# TSAL.net
KiCad netlist of a schematic drawn in Altium Designer
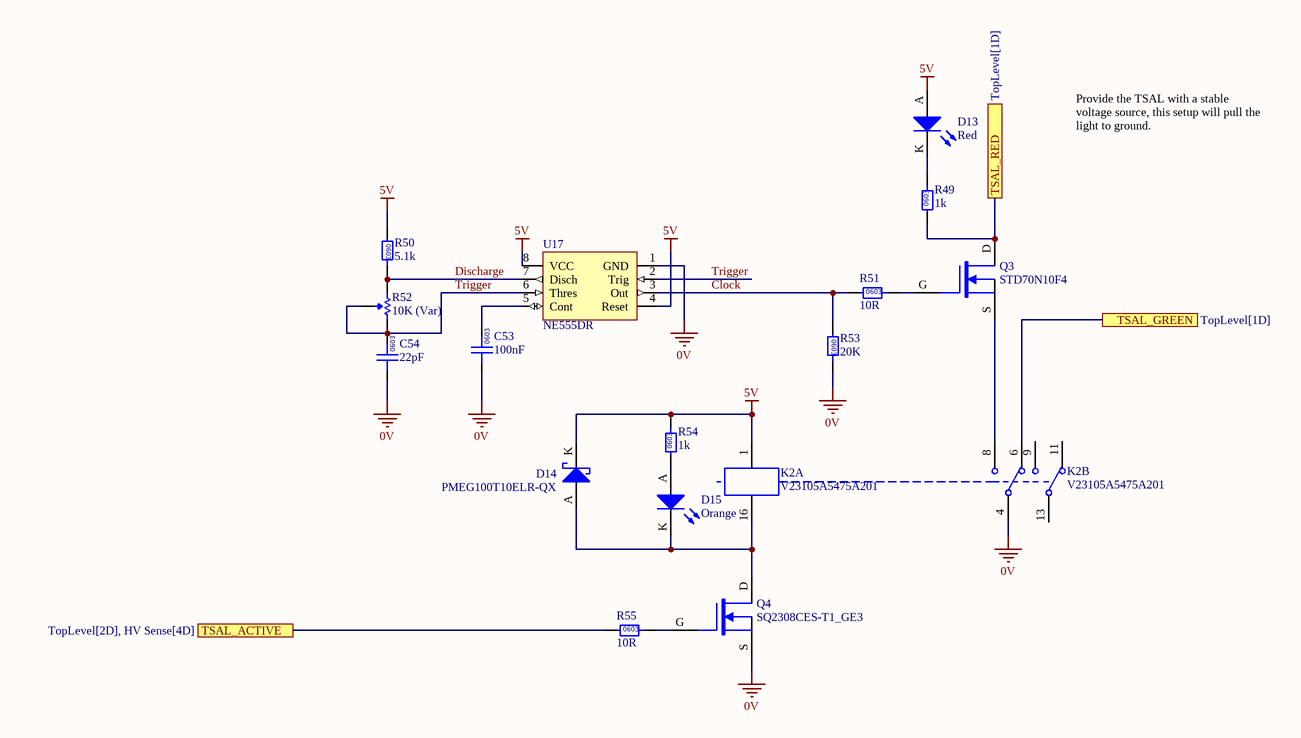
[diagram p0: TSAL.SchDoc]

(export (version "E")
  (design (tool "Eeschema 10.0.6"))
  (components
    (comp (ref "C53")
      (value "100nF")
      (footprint "0603")
      (fields
        (field (name "PART NUMBER") "GCM188L81H104KA57D")
        (field (name "MANUFACTURER") "muRata")
        (field (name "TOLERANCE") "±10%")
      )
      (libsource (lib "ts_standard_library") (part "Capacitor 0603"))
    )
    (comp (ref "C54")
      (value "22pF")
      (footprint "0603")
      (fields
        (field (name "PART NUMBER") "GRM0335C1H220JA01D")
        (field (name "MANUFACTURER") "Murata Electronics")
        (field (name "TOLERANCE") "±5%")
      )
      (libsource (lib "ts_standard_library") (part "Capacitor 0603"))
    )
    (comp (ref "D13")
      (value "Red")
      (footprint "0805 LED")
      (description "Red LED Indication - Discrete 1.75V 0805 (2012 Metric)")
      (fields (field (name "PART NUMBER") "SML-210LTT86") (field (name "MANUFACTURER") "ROHM Semiconductor"))
      (libsource (lib "ts_standard_library") (part "LED"))
    )
    (comp (ref "D14")
      (value "PMEG100T10ELR-QX")
      (footprint "NXP SOD123W")
      (fields
        (field (name "MANUFACTURER") "Nexperia USA Inc.")
        (field (name "DIGIKEY PART NUMBER") "1727-PMEG100T10ELR-QXCT-ND")
      )
      (libsource (lib "ts_standard_library") (part "Diode (Schottky)"))
    )
    (comp (ref "D15")
      (value "Orange")
      (footprint "0805 LED")
      (description "Orange LED Indication - Discrete 1.75V 0805 (2012 Metric)")
      (fields (field (name "PART NUMBER") "SML-211DTT86") (field (name "MANUFACTURER") "ROHM Semiconductor"))
      (libsource (lib "ts_standard_library") (part "LED"))
    )
    (comp (ref "K2")
      (value "V23105A5475A201")
      (footprint "TI 2-DIL")
      (description "5V DPDT Relay 3A 220VDC")
      (libsource (lib "") (part "Symbol_1"))
    )
    (comp (ref "Q3")
      (value "STD70N10F4")
      (footprint "STM TO-252 MOSFET")
      (description "N-Channel 100V 60A (Tc) 125W (Tc) Surface Mount DPAK")
      (fields
        (field (name "MANUFACTURER") "STMicroelectronics")
        (field (name "DIGIKEY PART NUMBER") "497-8806-2-ND")
        (field (name "PUBLISHER") "Altium Limited")
      )
      (libsource (lib "ts_standard_library") (part "MOSFET-N"))
    )
    (comp (ref "Q4")
      (value "SQ2308CES-T1_GE3")
      (footprint "VSHY SOT-23-3")
      (description "MOSFET N-CH 60V 2.3A SOT23")
      (fields
        (field (name "MANUFACTURER") "Vishay Siliconix")
        (field (name "DIGIKEY PART NUMBER") "SQ2308CES-T1_GE3CT-ND")
        (field (name "PUBLISHER") "Altium Limited")
      )
      (libsource (lib "ts_standard_library") (part "MOSFET-N"))
    )
    (comp (ref "R49")
      (value "1k")
      (footprint "0603")
      (fields
        (field (name "PART NUMBER") "RC0603FR-071KL")
        (field (name "MANUFACTURER") "YAGEO")
        (field (name "TOLERANCE") "0.01")
      )
      (libsource (lib "ts_standard_library") (part "Resistor 0603"))
    )
    (comp (ref "R50")
      (value "5.1k")
      (footprint "0603")
      (fields
        (field (name "PART NUMBER") "RC0603JR-075K1L")
        (field (name "MANUFACTURER") "YAGEO")
        (field (name "TOLERANCE") "0.01")
      )
      (libsource (lib "ts_standard_library") (part "Resistor 0603"))
    )
    (comp (ref "R51")
      (value "10R")
      (footprint "0603")
      (fields
        (field (name "PART NUMBER") "RC0603FR-0710RL")
        (field (name "MANUFACTURER") "YAGEO")
        (field (name "TOLERANCE") "0.01")
      )
      (libsource (lib "ts_standard_library") (part "Resistor 0603"))
    )
    (comp (ref "R52")
      (value "10K (Var)")
      (footprint "B 3296")
      (fields
        (field (name "PART NUMBER") "3296W-1-103LF")
        (field (name "MANUFACTURER") "Bournes Inc")
        (field (name "TOLERANCE") "0.1")
      )
      (libsource (lib "ts_standard_library") (part "Resistor (Potentiometer)"))
    )
    (comp (ref "R53")
      (value "20K")
      (footprint "0603")
      (fields
        (field (name "PART NUMBER") "RC0603FR-0720KL")
        (field (name "MANUFACTURER") "YAGEO")
        (field (name "TOLERANCE") "0.01")
      )
      (libsource (lib "ts_standard_library") (part "Resistor 0603"))
    )
    (comp (ref "R54")
      (value "1k")
      (footprint "0603")
      (fields
        (field (name "PART NUMBER") "RC0603FR-071KL")
        (field (name "MANUFACTURER") "YAGEO")
        (field (name "TOLERANCE") "0.01")
      )
      (libsource (lib "ts_standard_library") (part "Resistor 0603"))
    )
    (comp (ref "R55")
      (value "10R")
      (footprint "0603")
      (fields
        (field (name "PART NUMBER") "RC0603FR-0710RL")
        (field (name "MANUFACTURER") "YAGEO")
        (field (name "TOLERANCE") "0.01")
      )
      (libsource (lib "ts_standard_library") (part "Resistor 0603"))
    )
    (comp (ref "U17")
      (value "NE555DR")
      (footprint "TI 8-SOIC")
      (description "IC OSC SGL TIMER 100KHZ 8-SOIC")
      (libsource (lib "Team Swinburne") (part "NE555DR"))
    )
  )
  (nets
    (net (code "1") (name "/Clock") (class "Default")
      (node (ref "R51") (pin "1") (pinfunction "1_1") (pintype "passive"))
      (node (ref "R53") (pin "1") (pinfunction "1_1") (pintype "passive"))
      (node (ref "U17") (pin "3") (pinfunction "Out_3") (pintype "output"))
    )
    (net (code "2") (name "/Discharge") (class "Default")
      (node (ref "R50") (pin "2") (pinfunction "2_2") (pintype "passive"))
      (node (ref "R52") (pin "3") (pinfunction "CW_3") (pintype "passive"))
      (node (ref "U17") (pin "7") (pinfunction "Disch_7") (pintype "output"))
    )
    (net (code "3") (name "/TSAL_ACTIVE") (class "Default")
      (node (ref "R55") (pin "1") (pinfunction "1_1") (pintype "passive"))
    )
    (net (code "4") (name "/TSAL_GREEN") (class "Default")
      (node (ref "K2") (pin "6") (pinfunction "6_6") (pintype "passive"))
    )
    (net (code "5") (name "/TSAL_RED") (class "Default")
      (node (ref "Q3") (pin "D") (pinfunction "D_D") (pintype "passive"))
      (node (ref "R49") (pin "1") (pinfunction "1_1") (pintype "passive"))
    )
    (net (code "6") (name "/Trigger") (class "Default")
      (node (ref "C54") (pin "2") (pinfunction "2_2") (pintype "passive"))
      (node (ref "R52") (pin "1") (pinfunction "CCW_1") (pintype "passive"))
      (node (ref "R52") (pin "2") (pinfunction "Wiper_2") (pintype "passive"))
      (node (ref "U17") (pin "2") (pinfunction "Trig_2") (pintype "input"))
      (node (ref "U17") (pin "6") (pinfunction "Thres_6") (pintype "input"))
    )
    (net (code "7") (name "0V") (class "Default")
      (node (ref "C53") (pin "1") (pinfunction "1_1") (pintype "passive"))
      (node (ref "C54") (pin "1") (pinfunction "1_1") (pintype "passive"))
      (node (ref "K2") (pin "4") (pinfunction "4_4") (pintype "passive"))
      (node (ref "Q4") (pin "S") (pinfunction "S_S") (pintype "passive"))
      (node (ref "R53") (pin "2") (pinfunction "2_2") (pintype "passive"))
      (node (ref "U17") (pin "1") (pinfunction "GND_1") (pintype "power_in"))
    )
    (net (code "8") (name "5V") (class "Default")
      (node (ref "D13") (pin "A") (pinfunction "A_A") (pintype "passive"))
      (node (ref "D14") (pin "K") (pinfunction "K_K") (pintype "passive"))
      (node (ref "K2") (pin "1") (pinfunction "1_1") (pintype "passive"))
      (node (ref "R50") (pin "1") (pinfunction "1_1") (pintype "passive"))
      (node (ref "R54") (pin "2") (pinfunction "2_2") (pintype "passive"))
      (node (ref "U17") (pin "4") (pinfunction "Reset_4") (pintype "passive"))
      (node (ref "U17") (pin "8") (pinfunction "VCC_8") (pintype "passive"))
    )
    (net (code "9") (name "Net-(D13-PadK)") (class "Default")
      (node (ref "D13") (pin "K") (pinfunction "K_K") (pintype "passive"))
      (node (ref "R49") (pin "2") (pinfunction "2_2") (pintype "passive"))
    )
    (net (code "10") (name "Net-(D14-PadA)") (class "Default")
      (node (ref "D14") (pin "A") (pinfunction "A_A") (pintype "passive"))
      (node (ref "D15") (pin "K") (pinfunction "K_K") (pintype "passive"))
      (node (ref "K2") (pin "16") (pinfunction "16_16") (pintype "passive"))
      (node (ref "Q4") (pin "D") (pinfunction "D_D") (pintype "passive"))
    )
    (net (code "11") (name "Net-(D15-PadA)") (class "Default")
      (node (ref "D15") (pin "A") (pinfunction "A_A") (pintype "passive"))
      (node (ref "R54") (pin "1") (pinfunction "1_1") (pintype "passive"))
    )
    (net (code "12") (name "Net-(K2-Pad8)") (class "Default")
      (node (ref "K2") (pin "8") (pinfunction "8_8") (pintype "passive"))
      (node (ref "Q3") (pin "S") (pinfunction "S_S") (pintype "passive"))
    )
    (net (code "13") (name "Net-(Q3-PadG)") (class "Default")
      (node (ref "Q3") (pin "G") (pinfunction "G_G") (pintype "passive"))
      (node (ref "R51") (pin "2") (pinfunction "2_2") (pintype "passive"))
    )
    (net (code "14") (name "Net-(Q4-PadG)") (class "Default")
      (node (ref "Q4") (pin "G") (pinfunction "G_G") (pintype "passive"))
      (node (ref "R55") (pin "2") (pinfunction "2_2") (pintype "passive"))
    )
    (net (code "15") (name "Net-(U17-Cont)") (class "Default")
      (node (ref "C53") (pin "2") (pinfunction "2_2") (pintype "passive"))
      (node (ref "U17") (pin "5") (pinfunction "Cont_5") (pintype "bidirectional"))
    )
    (net (code "16") (name "unconnected-(K2-Pad9)") (class "Default")
      (node (ref "K2") (pin "9") (pinfunction "9_9") (pintype "passive"))
    )
    (net (code "17") (name "unconnected-(K2-Pad11)") (class "Default")
      (node (ref "K2") (pin "11") (pinfunction "11_11") (pintype "passive"))
    )
    (net (code "18") (name "unconnected-(K2-Pad13)") (class "Default")
      (node (ref "K2") (pin "13") (pinfunction "13_13") (pintype "passive"))
    )
  )
)
